# ssslidar_v0_1_blade_SIG.net
KiCad netlist of a schematic drawn in EAGLE
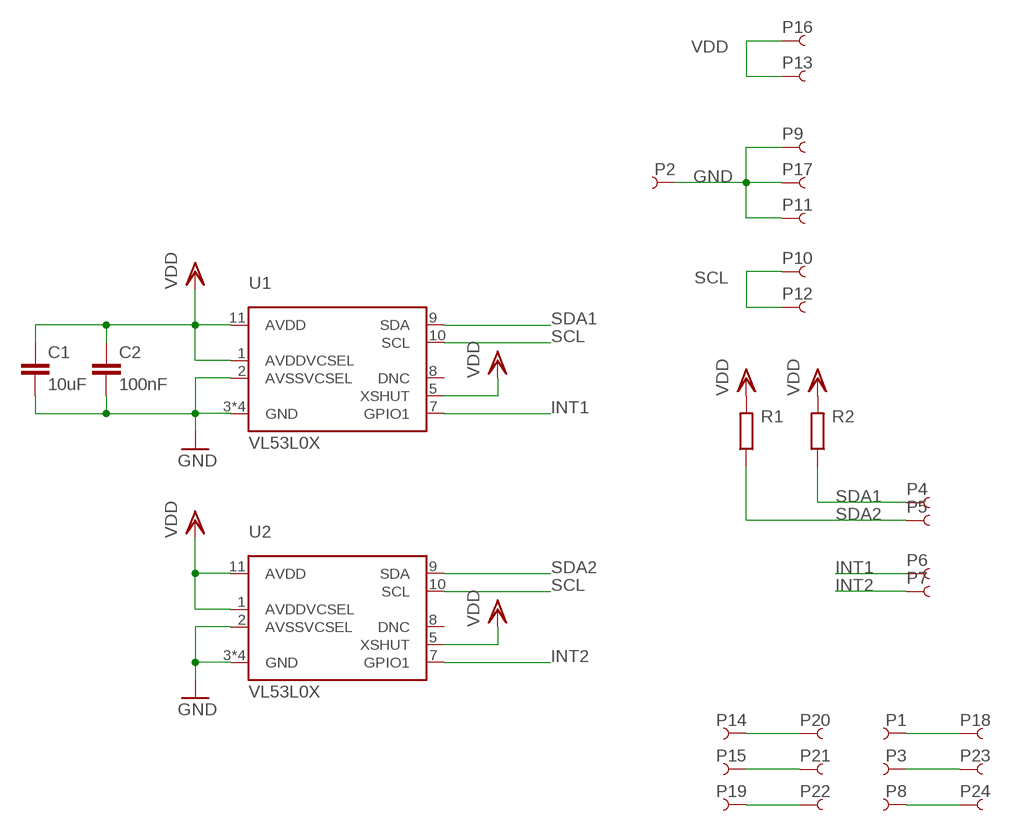
[diagram p0: schematic, sheet 1]

(export (version "E")
  (design (tool "Eeschema 10.0.6"))
  (components
    (comp (ref "C1")
      (value "10uF")
      (footprint "eagle-import:0805_N")
      (libsource (lib "eagle-import") (part "C0805"))
    )
    (comp (ref "C2")
      (value "100nF")
      (footprint "eagle-import:0402_N")
      (libsource (lib "eagle-import") (part "C0402"))
    )
    (comp (ref "P1")
      (value "PIN_SMD_0.8X1_RECT")
      (footprint "eagle-import:PIN_SMD_0.8X1_RECT")
      (libsource (lib "eagle-import") (part "PIN_SMD_0.8X1_RECT"))
    )
    (comp (ref "P2")
      (value "PIN_SMD_1X1_RECT")
      (footprint "eagle-import:PIN_SMD_1X1_RECT")
      (libsource (lib "eagle-import") (part "PIN_SMD_1X1_RECT"))
    )
    (comp (ref "P3")
      (value "PIN_SMD_0.8X1_RECT")
      (footprint "eagle-import:PIN_SMD_0.8X1_RECT")
      (libsource (lib "eagle-import") (part "PIN_SMD_0.8X1_RECT"))
    )
    (comp (ref "P4")
      (value "PIN_SMD_0.8X1_RECT")
      (footprint "eagle-import:PIN_SMD_0.8X1_RECT")
      (libsource (lib "eagle-import") (part "PIN_SMD_0.8X1_RECT"))
    )
    (comp (ref "P5")
      (value "PIN_SMD_0.8X1_RECT")
      (footprint "eagle-import:PIN_SMD_0.8X1_RECT")
      (libsource (lib "eagle-import") (part "PIN_SMD_0.8X1_RECT"))
    )
    (comp (ref "P6")
      (value "PIN_SMD_0.8X1_RECT")
      (footprint "eagle-import:PIN_SMD_0.8X1_RECT")
      (libsource (lib "eagle-import") (part "PIN_SMD_0.8X1_RECT"))
    )
    (comp (ref "P7")
      (value "PIN_SMD_0.8X1_RECT")
      (footprint "eagle-import:PIN_SMD_0.8X1_RECT")
      (libsource (lib "eagle-import") (part "PIN_SMD_0.8X1_RECT"))
    )
    (comp (ref "P8")
      (value "PIN_SMD_0.8X1_RECT")
      (footprint "eagle-import:PIN_SMD_0.8X1_RECT")
      (libsource (lib "eagle-import") (part "PIN_SMD_0.8X1_RECT"))
    )
    (comp (ref "P9")
      (value "PIN_SMD_1X1_RECT")
      (footprint "eagle-import:PIN_SMD_1X1_RECT")
      (libsource (lib "eagle-import") (part "PIN_SMD_1X1_RECT"))
    )
    (comp (ref "P10")
      (value "PIN_SMD_0.8X1_RECT")
      (footprint "eagle-import:PIN_SMD_0.8X1_RECT")
      (libsource (lib "eagle-import") (part "PIN_SMD_0.8X1_RECT"))
    )
    (comp (ref "P11")
      (value "PIN_SMD_1X1_RECT")
      (footprint "eagle-import:PIN_SMD_1X1_RECT")
      (libsource (lib "eagle-import") (part "PIN_SMD_1X1_RECT"))
    )
    (comp (ref "P12")
      (value "PIN_SMD_0.8X1_RECT")
      (footprint "eagle-import:PIN_SMD_0.8X1_RECT")
      (libsource (lib "eagle-import") (part "PIN_SMD_0.8X1_RECT"))
    )
    (comp (ref "P13")
      (value "PIN_SMD_0.8X1_RECT")
      (footprint "eagle-import:PIN_SMD_0.8X1_RECT")
      (libsource (lib "eagle-import") (part "PIN_SMD_0.8X1_RECT"))
    )
    (comp (ref "P14")
      (value "PIN_SMD_0.8X1_RECT")
      (footprint "eagle-import:PIN_SMD_0.8X1_RECT")
      (libsource (lib "eagle-import") (part "PIN_SMD_0.8X1_RECT"))
    )
    (comp (ref "P15")
      (value "PIN_SMD_0.8X1_RECT")
      (footprint "eagle-import:PIN_SMD_0.8X1_RECT")
      (libsource (lib "eagle-import") (part "PIN_SMD_0.8X1_RECT"))
    )
    (comp (ref "P16")
      (value "PIN_SMD_0.8X1_RECT")
      (footprint "eagle-import:PIN_SMD_0.8X1_RECT")
      (libsource (lib "eagle-import") (part "PIN_SMD_0.8X1_RECT"))
    )
    (comp (ref "P17")
      (value "PIN_SMD_1X1_RECT")
      (footprint "eagle-import:PIN_SMD_1X1_RECT")
      (libsource (lib "eagle-import") (part "PIN_SMD_1X1_RECT"))
    )
    (comp (ref "P18")
      (value "PIN_SMD_0.8X1_RECT")
      (footprint "eagle-import:PIN_SMD_0.8X1_RECT")
      (libsource (lib "eagle-import") (part "PIN_SMD_0.8X1_RECT"))
    )
    (comp (ref "P19")
      (value "PIN_SMD_0.8X1_RECT")
      (footprint "eagle-import:PIN_SMD_0.8X1_RECT")
      (libsource (lib "eagle-import") (part "PIN_SMD_0.8X1_RECT"))
    )
    (comp (ref "P20")
      (value "PIN_SMD_0.8X1_RECT")
      (footprint "eagle-import:PIN_SMD_0.8X1_RECT")
      (libsource (lib "eagle-import") (part "PIN_SMD_0.8X1_RECT"))
    )
    (comp (ref "P21")
      (value "PIN_SMD_0.8X1_RECT")
      (footprint "eagle-import:PIN_SMD_0.8X1_RECT")
      (libsource (lib "eagle-import") (part "PIN_SMD_0.8X1_RECT"))
    )
    (comp (ref "P22")
      (value "PIN_SMD_0.8X1_RECT")
      (footprint "eagle-import:PIN_SMD_0.8X1_RECT")
      (libsource (lib "eagle-import") (part "PIN_SMD_0.8X1_RECT"))
    )
    (comp (ref "P23")
      (value "PIN_SMD_0.8X1_RECT")
      (footprint "eagle-import:PIN_SMD_0.8X1_RECT")
      (libsource (lib "eagle-import") (part "PIN_SMD_0.8X1_RECT"))
    )
    (comp (ref "P24")
      (value "PIN_SMD_0.8X1_RECT")
      (footprint "eagle-import:PIN_SMD_0.8X1_RECT")
      (libsource (lib "eagle-import") (part "PIN_SMD_0.8X1_RECT"))
    )
    (comp (ref "R1")
      (value "R0402")
      (footprint "eagle-import:0402_N")
      (libsource (lib "eagle-import") (part "R0402"))
    )
    (comp (ref "R2")
      (value "R0402")
      (footprint "eagle-import:0402_N")
      (libsource (lib "eagle-import") (part "R0402"))
    )
    (comp (ref "U1")
      (value "VL53L0X")
      (footprint "eagle-import:VL53L0X")
      (libsource (lib "eagle-import") (part "VL53L0X"))
    )
    (comp (ref "U2")
      (value "VL53L0X")
      (footprint "eagle-import:VL53L0X")
      (libsource (lib "eagle-import") (part "VL53L0X"))
    )
  )
  (nets
    (net (code "1") (name "/INT1") (class "Default")
      (node (ref "P6") (pin "PIN") (pinfunction "1_PIN") (pintype "bidirectional"))
      (node (ref "U1") (pin "7") (pinfunction "GPIO1_7") (pintype "bidirectional"))
    )
    (net (code "2") (name "/INT2") (class "Default")
      (node (ref "P7") (pin "PIN") (pinfunction "1_PIN") (pintype "bidirectional"))
      (node (ref "U2") (pin "7") (pinfunction "GPIO1_7") (pintype "bidirectional"))
    )
    (net (code "3") (name "/SCL") (class "Default")
      (node (ref "P10") (pin "PIN") (pinfunction "1_PIN") (pintype "bidirectional"))
      (node (ref "P12") (pin "PIN") (pinfunction "1_PIN") (pintype "bidirectional"))
      (node (ref "U1") (pin "10") (pinfunction "SCL_10") (pintype "bidirectional"))
      (node (ref "U2") (pin "10") (pinfunction "SCL_10") (pintype "bidirectional"))
    )
    (net (code "4") (name "/SDA1") (class "Default")
      (node (ref "P4") (pin "PIN") (pinfunction "1_PIN") (pintype "bidirectional"))
      (node (ref "R2") (pin "1") (pinfunction "1_1") (pintype "passive"))
      (node (ref "U1") (pin "9") (pinfunction "SDA_9") (pintype "bidirectional"))
    )
    (net (code "5") (name "/SDA2") (class "Default")
      (node (ref "P5") (pin "PIN") (pinfunction "1_PIN") (pintype "bidirectional"))
      (node (ref "R1") (pin "1") (pinfunction "1_1") (pintype "passive"))
      (node (ref "U2") (pin "9") (pinfunction "SDA_9") (pintype "bidirectional"))
    )
    (net (code "6") (name "GND") (class "Default")
      (node (ref "C1") (pin "2") (pinfunction "2_2") (pintype "passive"))
      (node (ref "C2") (pin "2") (pinfunction "2_2") (pintype "passive"))
      (node (ref "P11") (pin "PIN") (pinfunction "1_PIN") (pintype "bidirectional"))
      (node (ref "P17") (pin "PIN") (pinfunction "1_PIN") (pintype "bidirectional"))
      (node (ref "P2") (pin "PIN") (pinfunction "1_PIN") (pintype "bidirectional"))
      (node (ref "P9") (pin "PIN") (pinfunction "1_PIN") (pintype "bidirectional"))
      (node (ref "U1") (pin "12") (pinfunction "GND_12") (pintype "bidirectional"))
      (node (ref "U1") (pin "2") (pinfunction "AVSSVCSEL_2") (pintype "bidirectional"))
      (node (ref "U1") (pin "3") (pinfunction "GND_3") (pintype "bidirectional"))
      (node (ref "U1") (pin "4") (pinfunction "GND_4") (pintype "bidirectional"))
      (node (ref "U1") (pin "6") (pinfunction "GND_6") (pintype "bidirectional"))
      (node (ref "U2") (pin "12") (pinfunction "GND_12") (pintype "bidirectional"))
      (node (ref "U2") (pin "2") (pinfunction "AVSSVCSEL_2") (pintype "bidirectional"))
      (node (ref "U2") (pin "3") (pinfunction "GND_3") (pintype "bidirectional"))
      (node (ref "U2") (pin "4") (pinfunction "GND_4") (pintype "bidirectional"))
      (node (ref "U2") (pin "6") (pinfunction "GND_6") (pintype "bidirectional"))
    )
    (net (code "7") (name "Net-(P1-1)") (class "Default")
      (node (ref "P1") (pin "PIN") (pinfunction "1_PIN") (pintype "bidirectional"))
      (node (ref "P18") (pin "PIN") (pinfunction "1_PIN") (pintype "bidirectional"))
    )
    (net (code "8") (name "Net-(P14-1)") (class "Default")
      (node (ref "P14") (pin "PIN") (pinfunction "1_PIN") (pintype "bidirectional"))
      (node (ref "P20") (pin "PIN") (pinfunction "1_PIN") (pintype "bidirectional"))
    )
    (net (code "9") (name "Net-(P15-1)") (class "Default")
      (node (ref "P15") (pin "PIN") (pinfunction "1_PIN") (pintype "bidirectional"))
      (node (ref "P21") (pin "PIN") (pinfunction "1_PIN") (pintype "bidirectional"))
    )
    (net (code "10") (name "Net-(P19-1)") (class "Default")
      (node (ref "P19") (pin "PIN") (pinfunction "1_PIN") (pintype "bidirectional"))
      (node (ref "P22") (pin "PIN") (pinfunction "1_PIN") (pintype "bidirectional"))
    )
    (net (code "11") (name "Net-(P23-1)") (class "Default")
      (node (ref "P23") (pin "PIN") (pinfunction "1_PIN") (pintype "bidirectional"))
      (node (ref "P3") (pin "PIN") (pinfunction "1_PIN") (pintype "bidirectional"))
    )
    (net (code "12") (name "Net-(P24-1)") (class "Default")
      (node (ref "P24") (pin "PIN") (pinfunction "1_PIN") (pintype "bidirectional"))
      (node (ref "P8") (pin "PIN") (pinfunction "1_PIN") (pintype "bidirectional"))
    )
    (net (code "13") (name "VDD") (class "Default")
      (node (ref "C1") (pin "1") (pinfunction "1_1") (pintype "passive"))
      (node (ref "C2") (pin "1") (pinfunction "1_1") (pintype "passive"))
      (node (ref "P13") (pin "PIN") (pinfunction "1_PIN") (pintype "bidirectional"))
      (node (ref "P16") (pin "PIN") (pinfunction "1_PIN") (pintype "bidirectional"))
      (node (ref "R1") (pin "2") (pinfunction "2_2") (pintype "passive"))
      (node (ref "R2") (pin "2") (pinfunction "2_2") (pintype "passive"))
      (node (ref "U1") (pin "1") (pinfunction "AVDDVCSEL_1") (pintype "bidirectional"))
      (node (ref "U1") (pin "11") (pinfunction "AVDD_11") (pintype "bidirectional"))
      (node (ref "U1") (pin "5") (pinfunction "XSHUT_5") (pintype "bidirectional"))
      (node (ref "U2") (pin "1") (pinfunction "AVDDVCSEL_1") (pintype "bidirectional"))
      (node (ref "U2") (pin "11") (pinfunction "AVDD_11") (pintype "bidirectional"))
      (node (ref "U2") (pin "5") (pinfunction "XSHUT_5") (pintype "bidirectional"))
    )
    (net (code "14") (name "unconnected-(U1-DNC-Pad8)") (class "Default")
      (node (ref "U1") (pin "8") (pinfunction "DNC_8") (pintype "bidirectional"))
    )
    (net (code "15") (name "unconnected-(U2-DNC-Pad8)") (class "Default")
      (node (ref "U2") (pin "8") (pinfunction "DNC_8") (pintype "bidirectional"))
    )
  )
)
